# Arduino_FPGA_Design.net
KiCad netlist of a schematic drawn in Altium Designer
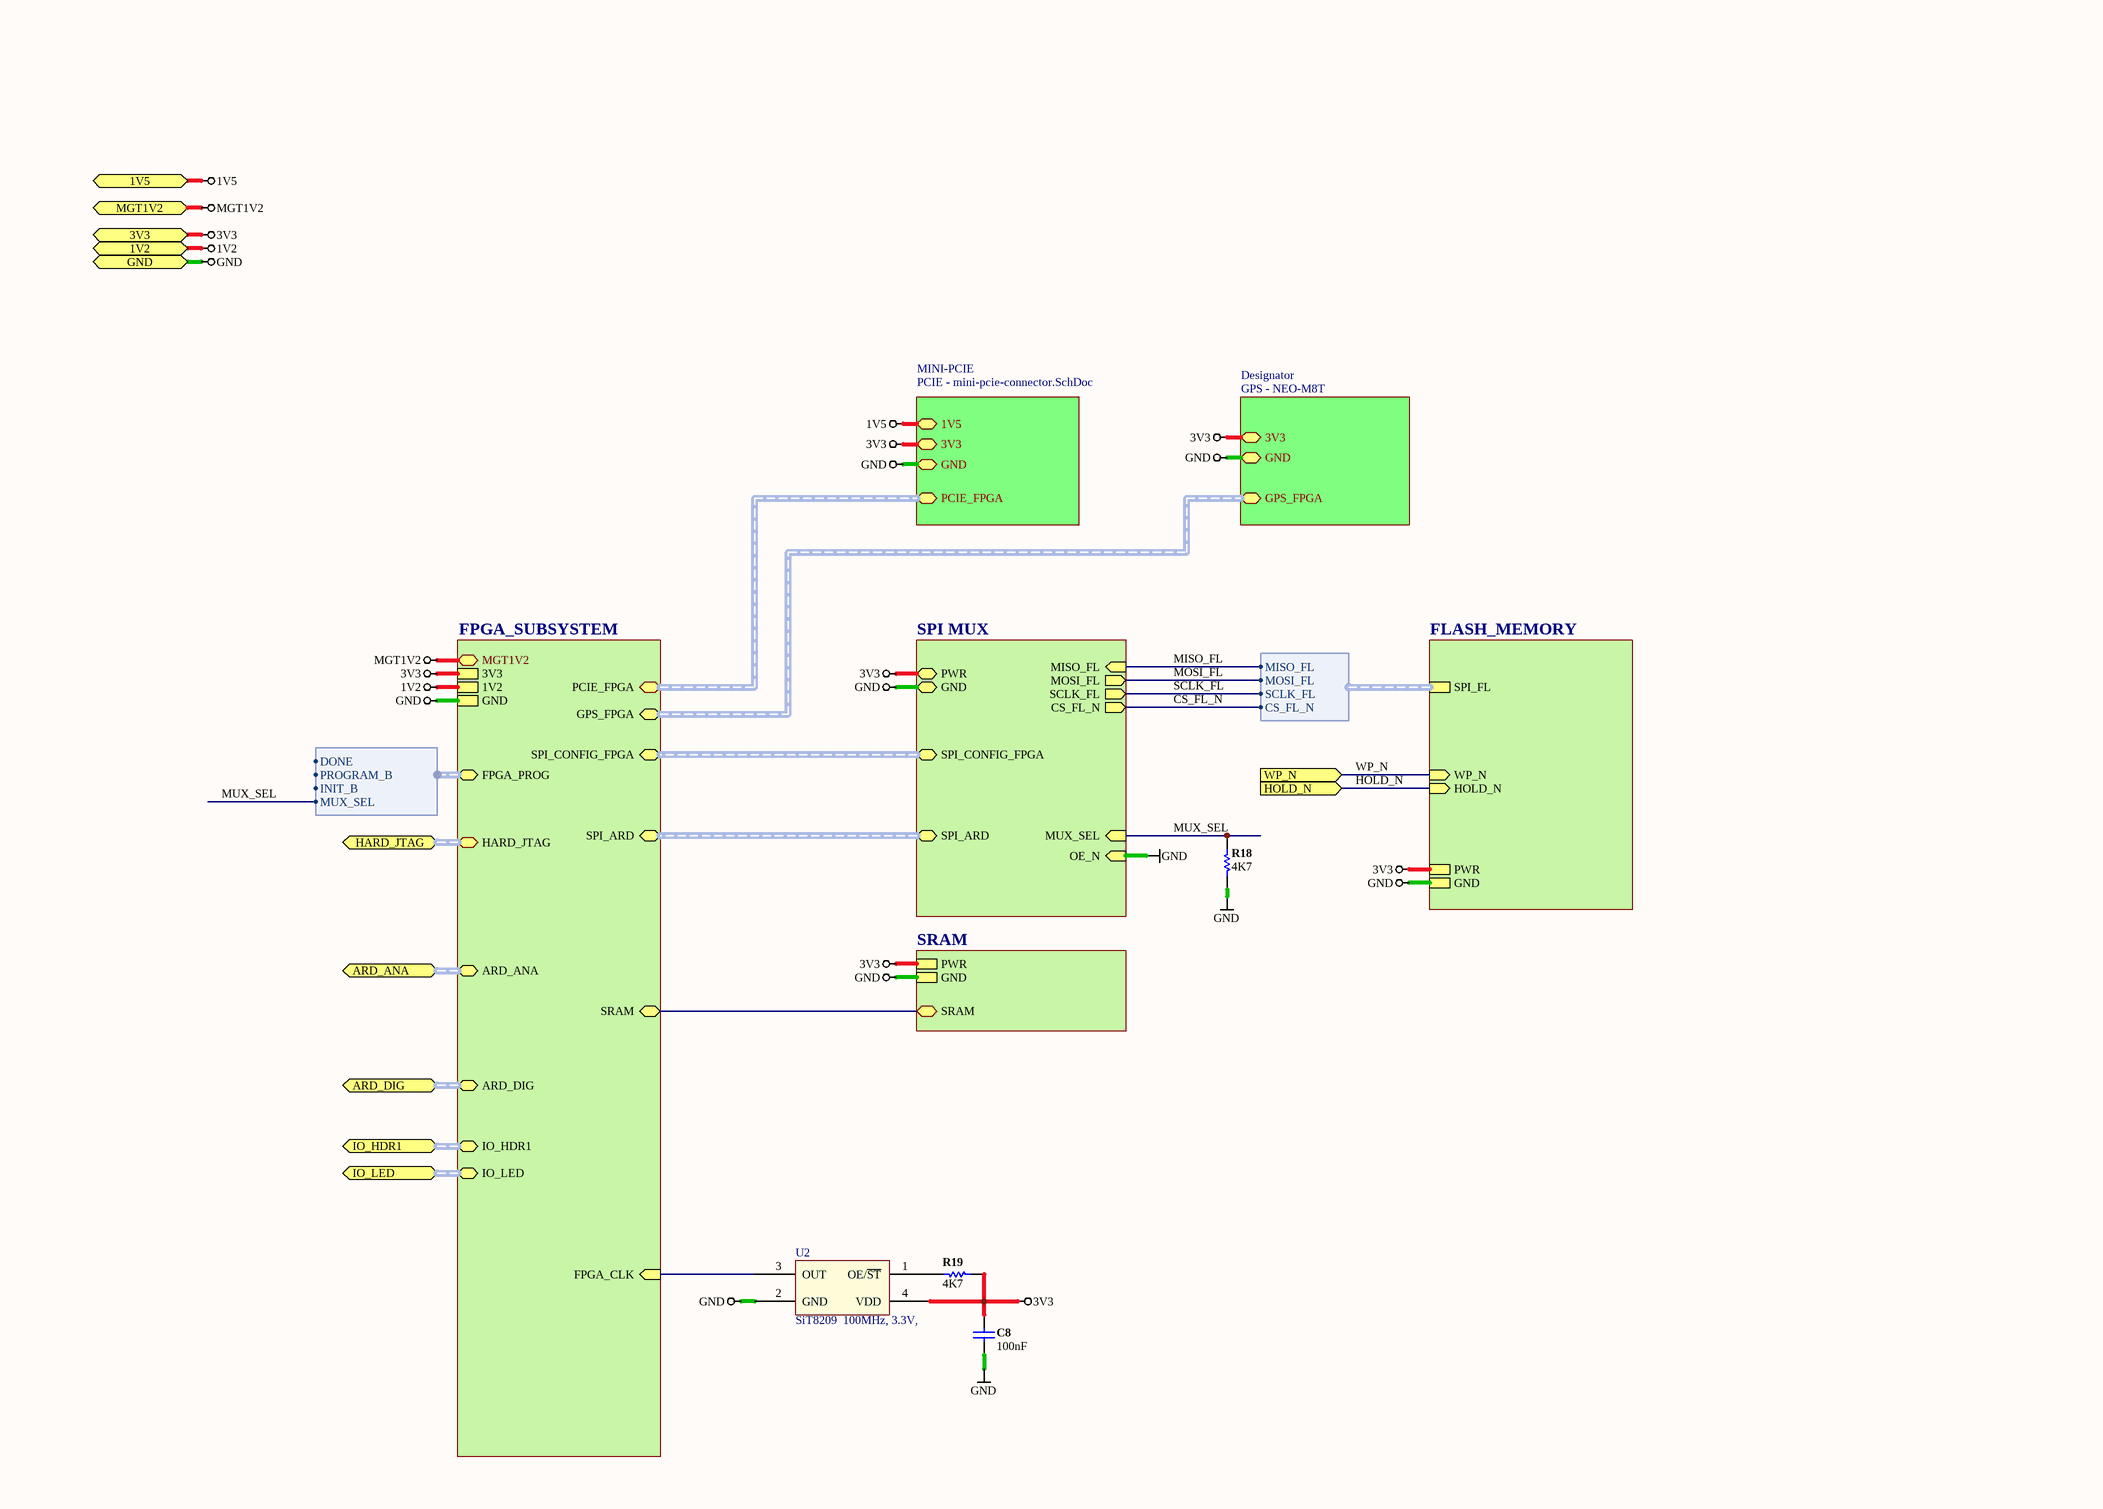
[diagram p0: Arduino FPGA Design.SchDoc]

(export (version "E")
  (design (tool "Eeschema 10.0.6"))
  (components
    (comp (ref "C8")
      (value "100nF")
      (footprint "CAPC0402(1005)60_L")
      (fields
        (field (name "TOLERANCE") "±10%")
        (field (name "MANUFACTURER PART NUMBER") "C0402C104K8PACTU")
        (field (name "Comment") "CAP 100nF 16V 0402(1005)")
      )
      (libsource (lib "Component_Database") (part "CAP_NP"))
    )
    (comp (ref "R18")
      (value "4K7")
      (footprint "RESC0402(1005)40_L")
      (fields
        (field (name "POWER") "1/16 W")
        (field (name "MANUFACTURER PART NUMBER") "CR0402-FX-4701GLFDKR-ND")
        (field (name "Comment") "4K7 1 0402")
      )
      (libsource (lib "Component_Database") (part "RES"))
    )
    (comp (ref "R19")
      (value "4K7")
      (footprint "RESC0402(1005)40_L")
      (fields
        (field (name "POWER") "1/16 W")
        (field (name "MANUFACTURER PART NUMBER") "CR0402-FX-4701GLFDKR-ND")
        (field (name "Comment") "4K7 1 0402")
      )
      (libsource (lib "Component_Database") (part "RES"))
    )
    (comp (ref "U2") (value "SiT8209  100MHz, 3.3V,") (libsource (lib "SIT8209") (part "SiT8209")))
  )
  (nets
    (net (code "11") (name "/FPGA_CLK") (class "Default")
      (node (ref "U2") (pin "3") (pinfunction "OUT_3") (pintype "passive"))
    )
    (net (code "19") (name "/MUX_SEL") (class "Default")
      (node (ref "R18") (pin "2") (pinfunction "2_2") (pintype "passive"))
    )
    (net (code "30") (name "3V3") (class "Default")
      (node (ref "C8") (pin "1") (pinfunction "1_1") (pintype "passive"))
      (node (ref "R19") (pin "2") (pinfunction "2_2") (pintype "passive"))
      (node (ref "U2") (pin "4") (pinfunction "VDD_4") (pintype "passive"))
    )
    (net (code "31") (name "GND") (class "Default")
      (node (ref "C8") (pin "2") (pinfunction "2_2") (pintype "passive"))
      (node (ref "R18") (pin "1") (pinfunction "1_1") (pintype "passive"))
      (node (ref "U2") (pin "2") (pinfunction "GND_2") (pintype "passive"))
    )
    (net (code "33") (name "Net-(U2-OE{slash}~{ST})") (class "Default")
      (node (ref "R19") (pin "1") (pinfunction "1_1") (pintype "passive"))
      (node (ref "U2") (pin "1") (pinfunction "OE/~{ST}_1") (pintype "passive"))
    )
  )
)
